# RF-Remute-FT-V1_1.net
KiCad netlist of a schematic drawn in Altium Designer
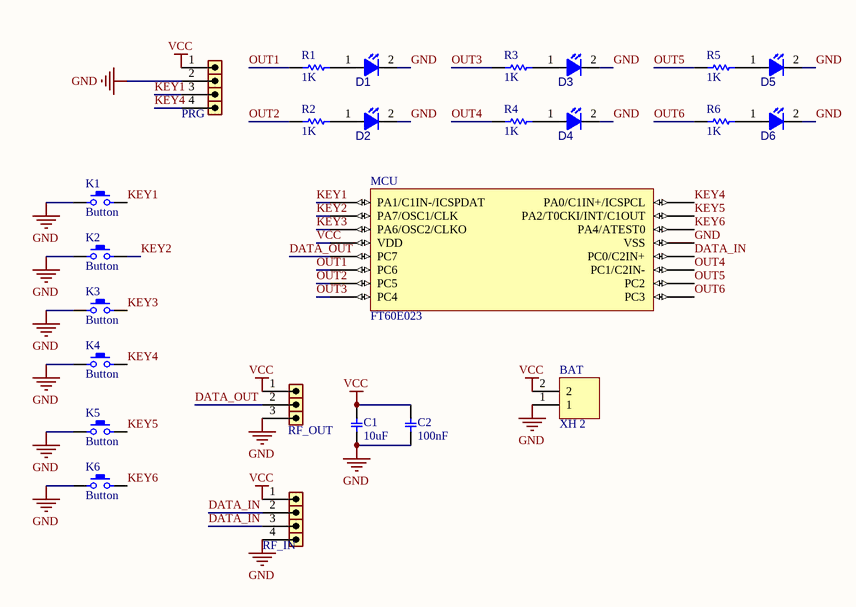
[diagram p0: RF-Remute-FT-V1.1.SchDoc]

(export (version "E")
  (design (tool "Eeschema 10.0.6"))
  (components
    (comp (ref "BAT")
      (value "XH 2")
      (footprint "XH 2 PIN ( White )")
      (description "Conector XH 2 Pin")
      (libsource (lib "XH Connector") (part "Conector XH 2 Pin"))
    )
    (comp (ref "C1")
      (value "10uF")
      (footprint "C0805")
      (description "Capacitor C SMD 0805")
      (fields (field (name "Comment") "Capacitor SMD 0805"))
      (libsource (lib "Capacitor") (part "Capacitor SMD 0805"))
    )
    (comp (ref "C2")
      (value "100nF")
      (footprint "C0805")
      (description "Capacitor C SMD 0805")
      (fields (field (name "Comment") "Capacitor SMD 0805"))
      (libsource (lib "Capacitor") (part "Capacitor SMD 0805"))
    )
    (comp (ref "D1")
      (value "LED SMD 0805")
      (footprint "LED SMD 0805 (Green)")
      (libsource (lib "LED") (part "LED SMD 0805"))
    )
    (comp (ref "D2")
      (value "LED SMD 0805")
      (footprint "LED SMD 0805 (Green)")
      (libsource (lib "LED") (part "LED SMD 0805"))
    )
    (comp (ref "D3")
      (value "LED SMD 0805")
      (footprint "LED SMD 0805 (Green)")
      (libsource (lib "LED") (part "LED SMD 0805"))
    )
    (comp (ref "D4")
      (value "LED SMD 0805")
      (footprint "LED SMD 0805 (Green)")
      (libsource (lib "LED") (part "LED SMD 0805"))
    )
    (comp (ref "D5")
      (value "LED SMD 0805")
      (footprint "LED SMD 0805 (Green)")
      (libsource (lib "LED") (part "LED SMD 0805"))
    )
    (comp (ref "D6")
      (value "LED SMD 0805")
      (footprint "LED SMD 0805 (Green)")
      (libsource (lib "LED") (part "LED SMD 0805"))
    )
    (comp (ref "K1")
      (value "Button")
      (footprint "BUTTON")
      (fields
        (field (name "MANUFACTURER") "Panasonic")
        (field (name "MANUFACTURER PART NUMBER") "EVQ-PE605T")
      )
      (libsource (lib "LIBM") (part "BUTTON-6.3.4-SMD"))
    )
    (comp (ref "K2")
      (value "Button")
      (footprint "BUTTON")
      (fields
        (field (name "MANUFACTURER") "Panasonic")
        (field (name "MANUFACTURER PART NUMBER") "EVQ-PE605T")
      )
      (libsource (lib "LIBM") (part "BUTTON-6.3.4-SMD"))
    )
    (comp (ref "K3")
      (value "Button")
      (footprint "BUTTON")
      (fields
        (field (name "MANUFACTURER") "Panasonic")
        (field (name "MANUFACTURER PART NUMBER") "EVQ-PE605T")
      )
      (libsource (lib "LIBM") (part "BUTTON-6.3.4-SMD"))
    )
    (comp (ref "K4")
      (value "Button")
      (footprint "BUTTON")
      (fields
        (field (name "MANUFACTURER") "Panasonic")
        (field (name "MANUFACTURER PART NUMBER") "EVQ-PE605T")
      )
      (libsource (lib "LIBM") (part "BUTTON-6.3.4-SMD"))
    )
    (comp (ref "K5")
      (value "Button")
      (footprint "BUTTON")
      (fields
        (field (name "MANUFACTURER") "Panasonic")
        (field (name "MANUFACTURER PART NUMBER") "EVQ-PE605T")
      )
      (libsource (lib "LIBM") (part "BUTTON-6.3.4-SMD"))
    )
    (comp (ref "K6")
      (value "Button")
      (footprint "BUTTON")
      (fields
        (field (name "MANUFACTURER") "Panasonic")
        (field (name "MANUFACTURER PART NUMBER") "EVQ-PE605T")
      )
      (libsource (lib "LIBM") (part "BUTTON-6.3.4-SMD"))
    )
    (comp (ref "MCU") (value "FT60E023") (footprint "SSOP-16") (libsource (lib "HOLTEK") (part "FT60E023")))
    (comp (ref "PRG")
      (value "Female Header Single 4")
      (footprint "HDR_F_1X4")
      (description "Female, pitch: 2.54mm")
      (libsource (lib "Header") (part "Female Header Single 4"))
    )
    (comp (ref "R1")
      (value "1K")
      (footprint "R0805")
      (description "Resistor SMD 0805")
      (libsource (lib "Resistor") (part "Resistor SMD 0805"))
    )
    (comp (ref "R2")
      (value "1K")
      (footprint "R0805")
      (description "Resistor SMD 0805")
      (libsource (lib "Resistor") (part "Resistor SMD 0805"))
    )
    (comp (ref "R3")
      (value "1K")
      (footprint "R0805")
      (description "Resistor SMD 0805")
      (libsource (lib "Resistor") (part "Resistor SMD 0805"))
    )
    (comp (ref "R4")
      (value "1K")
      (footprint "R0805")
      (description "Resistor SMD 0805")
      (libsource (lib "Resistor") (part "Resistor SMD 0805"))
    )
    (comp (ref "R5")
      (value "1K")
      (footprint "R0805")
      (description "Resistor SMD 0805")
      (libsource (lib "Resistor") (part "Resistor SMD 0805"))
    )
    (comp (ref "R6")
      (value "1K")
      (footprint "R0805")
      (description "Resistor SMD 0805")
      (libsource (lib "Resistor") (part "Resistor SMD 0805"))
    )
    (comp (ref "RF_IN")
      (value "Female Header Single 4")
      (footprint "HDR_F_1X4")
      (description "Female, pitch: 2.54mm")
      (libsource (lib "Header") (part "Female Header Single 4"))
    )
    (comp (ref "RF_OUT")
      (value "Female Header Single 3")
      (footprint "HDR_F_1X3")
      (description "Female, pitch: 2.54mm")
      (libsource (lib "Header") (part "Female Header Single 3"))
    )
  )
  (nets
    (net (code "1") (name "/DATA_IN") (class "Default")
      (node (ref "MCU") (pin "12") (pinfunction "PC0/C2IN+_12") (pintype "bidirectional"))
      (node (ref "RF_IN") (pin "2") (pinfunction "2_2") (pintype "passive"))
      (node (ref "RF_IN") (pin "3") (pinfunction "3_3") (pintype "passive"))
    )
    (net (code "2") (name "/DATA_OUT") (class "Default")
      (node (ref "MCU") (pin "5") (pinfunction "PC7_5") (pintype "bidirectional"))
      (node (ref "RF_OUT") (pin "2") (pinfunction "2_2") (pintype "passive"))
    )
    (net (code "3") (name "/KEY1") (class "Default")
      (node (ref "K1") (pin "2") (pinfunction "2_2") (pintype "passive"))
      (node (ref "MCU") (pin "1") (pinfunction "PA1/C1IN-/ICSPDAT_1") (pintype "bidirectional"))
      (node (ref "PRG") (pin "3") (pinfunction "3_3") (pintype "passive"))
    )
    (net (code "4") (name "/KEY2") (class "Default")
      (node (ref "K2") (pin "2") (pinfunction "2_2") (pintype "passive"))
      (node (ref "MCU") (pin "2") (pinfunction "PA7/OSC1/CLK_2") (pintype "bidirectional"))
    )
    (net (code "5") (name "/KEY3") (class "Default")
      (node (ref "K3") (pin "2") (pinfunction "2_2") (pintype "passive"))
      (node (ref "MCU") (pin "3") (pinfunction "PA6/OSC2/CLKO_3") (pintype "bidirectional"))
    )
    (net (code "6") (name "/KEY4") (class "Default")
      (node (ref "K4") (pin "2") (pinfunction "2_2") (pintype "passive"))
      (node (ref "MCU") (pin "16") (pinfunction "PA0/C1IN+/ICSPCL_16") (pintype "bidirectional"))
      (node (ref "PRG") (pin "4") (pinfunction "4_4") (pintype "passive"))
    )
    (net (code "7") (name "/KEY5") (class "Default")
      (node (ref "K5") (pin "2") (pinfunction "2_2") (pintype "passive"))
      (node (ref "MCU") (pin "15") (pinfunction "PA2/T0CKI/INT/C1OUT_15") (pintype "bidirectional"))
    )
    (net (code "8") (name "/KEY6") (class "Default")
      (node (ref "K6") (pin "2") (pinfunction "2_2") (pintype "passive"))
      (node (ref "MCU") (pin "14") (pinfunction "PA4/ATEST0_14") (pintype "bidirectional"))
    )
    (net (code "9") (name "/OUT1") (class "Default")
      (node (ref "MCU") (pin "6") (pinfunction "PC6_6") (pintype "bidirectional"))
      (node (ref "R1") (pin "2") (pinfunction "2_2") (pintype "passive"))
    )
    (net (code "10") (name "/OUT2") (class "Default")
      (node (ref "MCU") (pin "7") (pinfunction "PC5_7") (pintype "bidirectional"))
      (node (ref "R2") (pin "2") (pinfunction "2_2") (pintype "passive"))
    )
    (net (code "11") (name "/OUT3") (class "Default")
      (node (ref "MCU") (pin "8") (pinfunction "PC4_8") (pintype "bidirectional"))
      (node (ref "R3") (pin "2") (pinfunction "2_2") (pintype "passive"))
    )
    (net (code "12") (name "/OUT4") (class "Default")
      (node (ref "MCU") (pin "11") (pinfunction "PC1/C2IN-_11") (pintype "bidirectional"))
      (node (ref "R4") (pin "2") (pinfunction "2_2") (pintype "passive"))
    )
    (net (code "13") (name "/OUT5") (class "Default")
      (node (ref "MCU") (pin "10") (pinfunction "PC2_10") (pintype "bidirectional"))
      (node (ref "R5") (pin "2") (pinfunction "2_2") (pintype "passive"))
    )
    (net (code "14") (name "/OUT6") (class "Default")
      (node (ref "MCU") (pin "9") (pinfunction "PC3_9") (pintype "bidirectional"))
      (node (ref "R6") (pin "2") (pinfunction "2_2") (pintype "passive"))
    )
    (net (code "15") (name "GND") (class "Default")
      (node (ref "BAT") (pin "1") (pinfunction "1_1") (pintype "passive"))
      (node (ref "C1") (pin "1") (pinfunction "1_1") (pintype "passive"))
      (node (ref "C2") (pin "1") (pinfunction "1_1") (pintype "passive"))
      (node (ref "D1") (pin "2") (pinfunction "CATHODE_2") (pintype "passive"))
      (node (ref "D2") (pin "2") (pinfunction "CATHODE_2") (pintype "passive"))
      (node (ref "D3") (pin "2") (pinfunction "CATHODE_2") (pintype "passive"))
      (node (ref "D4") (pin "2") (pinfunction "CATHODE_2") (pintype "passive"))
      (node (ref "D5") (pin "2") (pinfunction "CATHODE_2") (pintype "passive"))
      (node (ref "D6") (pin "2") (pinfunction "CATHODE_2") (pintype "passive"))
      (node (ref "K1") (pin "1") (pinfunction "1_1") (pintype "passive"))
      (node (ref "K2") (pin "1") (pinfunction "1_1") (pintype "passive"))
      (node (ref "K3") (pin "1") (pinfunction "1_1") (pintype "passive"))
      (node (ref "K4") (pin "1") (pinfunction "1_1") (pintype "passive"))
      (node (ref "K5") (pin "1") (pinfunction "1_1") (pintype "passive"))
      (node (ref "K6") (pin "1") (pinfunction "1_1") (pintype "passive"))
      (node (ref "MCU") (pin "13") (pinfunction "VSS_13") (pintype "bidirectional"))
      (node (ref "PRG") (pin "2") (pinfunction "2_2") (pintype "passive"))
      (node (ref "RF_IN") (pin "4") (pinfunction "4_4") (pintype "passive"))
      (node (ref "RF_OUT") (pin "3") (pinfunction "3_3") (pintype "passive"))
    )
    (net (code "16") (name "Net-(D1-ANODE)") (class "Default")
      (node (ref "D1") (pin "1") (pinfunction "ANODE_1") (pintype "passive"))
      (node (ref "R1") (pin "1") (pinfunction "1_1") (pintype "passive"))
    )
    (net (code "17") (name "Net-(D2-ANODE)") (class "Default")
      (node (ref "D2") (pin "1") (pinfunction "ANODE_1") (pintype "passive"))
      (node (ref "R2") (pin "1") (pinfunction "1_1") (pintype "passive"))
    )
    (net (code "18") (name "Net-(D3-ANODE)") (class "Default")
      (node (ref "D3") (pin "1") (pinfunction "ANODE_1") (pintype "passive"))
      (node (ref "R3") (pin "1") (pinfunction "1_1") (pintype "passive"))
    )
    (net (code "19") (name "Net-(D4-ANODE)") (class "Default")
      (node (ref "D4") (pin "1") (pinfunction "ANODE_1") (pintype "passive"))
      (node (ref "R4") (pin "1") (pinfunction "1_1") (pintype "passive"))
    )
    (net (code "20") (name "Net-(D5-ANODE)") (class "Default")
      (node (ref "D5") (pin "1") (pinfunction "ANODE_1") (pintype "passive"))
      (node (ref "R5") (pin "1") (pinfunction "1_1") (pintype "passive"))
    )
    (net (code "21") (name "Net-(D6-ANODE)") (class "Default")
      (node (ref "D6") (pin "1") (pinfunction "ANODE_1") (pintype "passive"))
      (node (ref "R6") (pin "1") (pinfunction "1_1") (pintype "passive"))
    )
    (net (code "22") (name "VCC") (class "Default")
      (node (ref "BAT") (pin "2") (pinfunction "2_2") (pintype "passive"))
      (node (ref "C1") (pin "2") (pinfunction "2_2") (pintype "passive"))
      (node (ref "C2") (pin "2") (pinfunction "2_2") (pintype "passive"))
      (node (ref "MCU") (pin "4") (pinfunction "VDD_4") (pintype "bidirectional"))
      (node (ref "PRG") (pin "1") (pinfunction "1_1") (pintype "passive"))
      (node (ref "RF_IN") (pin "1") (pinfunction "1_1") (pintype "passive"))
      (node (ref "RF_OUT") (pin "1") (pinfunction "1_1") (pintype "passive"))
    )
  )
)
